# FPC-isoJTAG.net
KiCad netlist of a schematic drawn in Altium Designer
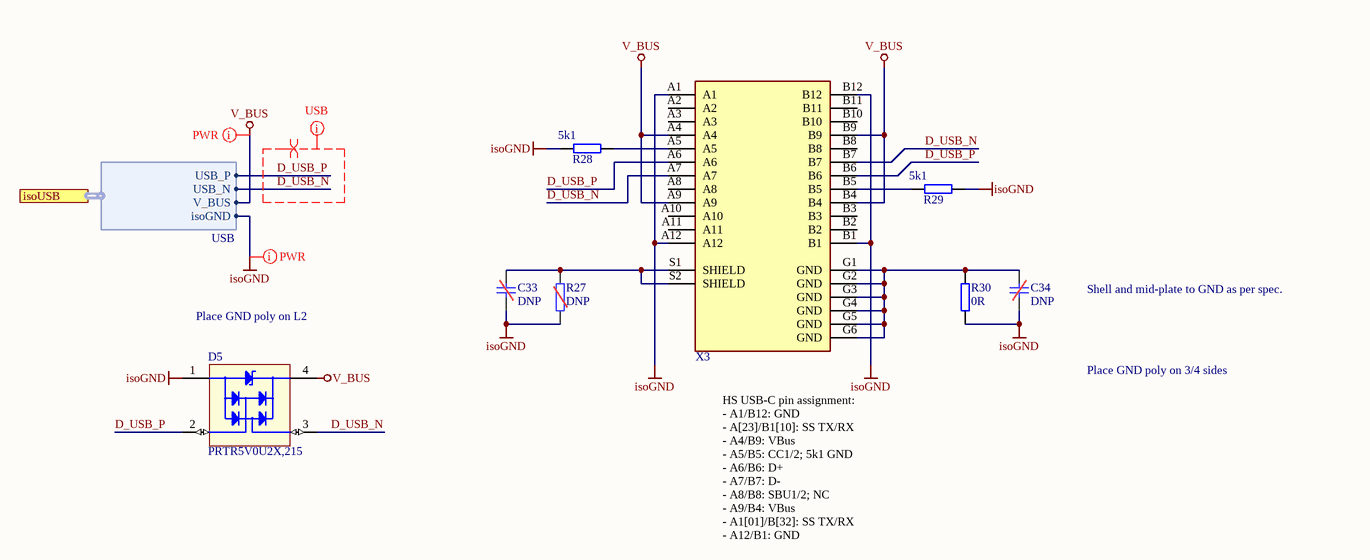
[diagram p0: FPC-isoJTAG.SchDoc]

(export (version "E")
  (design (tool "Eeschema 10.0.6"))
  (components
    (comp (ref "C33")
      (value "DNP")
      (footprint "C_1206_TE-DNP")
      (description "Generic capacitor (DNP)")
      (fields
        (field (name "MANUFACTURER PART NUMBER") "UZgen_C_1206_DNP")
        (field (name "MANUFACTURER") "UZgen")
        (field (name "CREATED FROM") "UZgenTool")
      )
      (libsource (lib "user") (part "CAP-NP-DNP"))
    )
    (comp (ref "C34")
      (value "DNP")
      (footprint "C_1206_TE-DNP")
      (description "Generic capacitor (DNP)")
      (fields
        (field (name "MANUFACTURER PART NUMBER") "UZgen_C_1206_DNP")
        (field (name "MANUFACTURER") "UZgen")
        (field (name "CREATED FROM") "UZgenTool")
      )
      (libsource (lib "user") (part "CAP-NP-DNP"))
    )
    (comp (ref "D5")
      (value "PRTR5V0U2X,215")
      (footprint "SOT-143B-4")
      (description "ESD Suppressors / TVS Diodes PRTR5V0U2X/SOT143/SOT4")
      (fields
        (field (name "MANUFACTURER") "Nexperia")
        (field (name "LCSC PART NUMBER") "C12333")
        (field (name "CREATED FROM") "AGeiger")
      )
      (libsource (lib "user") (part "CD143A-SRxx"))
    )
    (comp (ref "R27")
      (value "DNP")
      (footprint "R_1206_TE-DNP")
      (description "Generic resistor (DNP)")
      (fields
        (field (name "MANUFACTURER PART NUMBER") "UZgen_R_1206_DNP")
        (field (name "MANUFACTURER") "UZgen")
        (field (name "CREATED FROM") "UZgenTool")
      )
      (libsource (lib "user") (part "RES-DNP"))
    )
    (comp (ref "R28")
      (value "5k1")
      (footprint "R_0603_TE")
      (description "Generic resistor")
      (fields
        (field (name "MANUFACTURER PART NUMBER") "UZgen_R_0603_5k1")
        (field (name "MANUFACTURER") "UZgen")
        (field (name "CREATED FROM") "UZgenTool")
      )
      (libsource (lib "user") (part "RES"))
    )
    (comp (ref "R29")
      (value "5k1")
      (footprint "R_0603_TE")
      (description "Generic resistor")
      (fields
        (field (name "MANUFACTURER PART NUMBER") "UZgen_R_0603_5k1")
        (field (name "MANUFACTURER") "UZgen")
        (field (name "CREATED FROM") "UZgenTool")
      )
      (libsource (lib "user") (part "RES"))
    )
    (comp (ref "R30")
      (value "0R")
      (footprint "R_1206_TE")
      (description "Generic resistor")
      (fields
        (field (name "MANUFACTURER PART NUMBER") "UZgen_R_1206_0R")
        (field (name "MANUFACTURER") "UZgen")
        (field (name "CREATED FROM") "UZgenTool")
      )
      (libsource (lib "user") (part "RES"))
    )
    (comp (ref "X3")
      (value "~")
      (footprint "AMPHENOL_MUSBRM1C130_CUSTOMPADLEN3.05mm")
      (description "USB Connectors RUGGED TYPE C RIGHT ANGLE")
      (fields
        (field (name "MANUFACTURER PART NUMBER") "MUSBRM1C1M0")
        (field (name "MANUFACTURER") "Amphenol")
        (field (name "CREATED FROM") "FRosner")
      )
      (libsource (lib "user") (part "MUSBRM1C130"))
    )
  )
  (nets
    (net (code "2") (name "/D_USB_N") (class "Default")
      (node (ref "D5") (pin "3") (pinfunction "I/O_3") (pintype "bidirectional"))
      (node (ref "X3") (pin "A7") (pinfunction "A7_A7") (pintype "passive"))
      (node (ref "X3") (pin "B7") (pinfunction "B7_B7") (pintype "passive"))
    )
    (net (code "3") (name "/D_USB_P") (class "Default")
      (node (ref "D5") (pin "2") (pinfunction "I/O_2") (pintype "bidirectional"))
      (node (ref "X3") (pin "A6") (pinfunction "A6_A6") (pintype "passive"))
      (node (ref "X3") (pin "B6") (pinfunction "B6_B6") (pintype "passive"))
    )
    (net (code "5") (name "Net-(C33-Pad2)") (class "Default")
      (node (ref "C33") (pin "2") (pinfunction "2_2") (pintype "passive"))
      (node (ref "R27") (pin "2") (pinfunction "2_2") (pintype "passive"))
      (node (ref "X3") (pin "S1") (pinfunction "SHIELD_S1") (pintype "passive"))
      (node (ref "X3") (pin "S2") (pinfunction "SHIELD_S2") (pintype "passive"))
    )
    (net (code "6") (name "Net-(C34-Pad2)") (class "Default")
      (node (ref "C34") (pin "2") (pinfunction "2_2") (pintype "passive"))
      (node (ref "R30") (pin "2") (pinfunction "2_2") (pintype "passive"))
      (node (ref "X3") (pin "G1") (pinfunction "GND_G1") (pintype "power_in"))
      (node (ref "X3") (pin "G2") (pinfunction "GND_G2") (pintype "power_in"))
      (node (ref "X3") (pin "G3") (pinfunction "GND_G3") (pintype "power_in"))
      (node (ref "X3") (pin "G4") (pinfunction "GND_G4") (pintype "power_in"))
      (node (ref "X3") (pin "G5") (pinfunction "GND_G5") (pintype "power_in"))
      (node (ref "X3") (pin "G6") (pinfunction "GND_G6") (pintype "power_in"))
    )
    (net (code "7") (name "Net-(R28-Pad2)") (class "Default")
      (node (ref "R28") (pin "2") (pinfunction "2_2") (pintype "passive"))
      (node (ref "X3") (pin "A5") (pinfunction "A5_A5") (pintype "passive"))
    )
    (net (code "8") (name "Net-(R29-Pad1)") (class "Default")
      (node (ref "R29") (pin "1") (pinfunction "1_1") (pintype "passive"))
      (node (ref "X3") (pin "B5") (pinfunction "B5_B5") (pintype "passive"))
    )
    (net (code "9") (name "V_BUS") (class "Default")
      (node (ref "D5") (pin "4") (pinfunction "REF_4") (pintype "passive"))
      (node (ref "X3") (pin "A4") (pinfunction "A4_A4") (pintype "passive"))
      (node (ref "X3") (pin "A9") (pinfunction "A9_A9") (pintype "passive"))
      (node (ref "X3") (pin "B4") (pinfunction "B4_B4") (pintype "passive"))
      (node (ref "X3") (pin "B9") (pinfunction "B9_B9") (pintype "passive"))
    )
    (net (code "10") (name "isoGND") (class "Default")
      (node (ref "C33") (pin "1") (pinfunction "1_1") (pintype "passive"))
      (node (ref "C34") (pin "1") (pinfunction "1_1") (pintype "passive"))
      (node (ref "D5") (pin "1") (pinfunction "GND_1") (pintype "passive"))
      (node (ref "R27") (pin "1") (pinfunction "1_1") (pintype "passive"))
      (node (ref "R28") (pin "1") (pinfunction "1_1") (pintype "passive"))
      (node (ref "R29") (pin "2") (pinfunction "2_2") (pintype "passive"))
      (node (ref "R30") (pin "1") (pinfunction "1_1") (pintype "passive"))
      (node (ref "X3") (pin "A1") (pinfunction "A1_A1") (pintype "passive"))
      (node (ref "X3") (pin "A12") (pinfunction "A12_A12") (pintype "passive"))
      (node (ref "X3") (pin "B1") (pinfunction "B1_B1") (pintype "passive"))
      (node (ref "X3") (pin "B12") (pinfunction "B12_B12") (pintype "passive"))
    )
    (net (code "11") (name "unconnected-(X3-PadA2)") (class "Default")
      (node (ref "X3") (pin "A2") (pinfunction "A2_A2") (pintype "passive"))
    )
    (net (code "12") (name "unconnected-(X3-PadA3)") (class "Default")
      (node (ref "X3") (pin "A3") (pinfunction "A3_A3") (pintype "passive"))
    )
    (net (code "13") (name "unconnected-(X3-PadA8)") (class "Default")
      (node (ref "X3") (pin "A8") (pinfunction "A8_A8") (pintype "passive"))
    )
    (net (code "14") (name "unconnected-(X3-PadA10)") (class "Default")
      (node (ref "X3") (pin "A10") (pinfunction "A10_A10") (pintype "passive"))
    )
    (net (code "15") (name "unconnected-(X3-PadA11)") (class "Default")
      (node (ref "X3") (pin "A11") (pinfunction "A11_A11") (pintype "passive"))
    )
    (net (code "16") (name "unconnected-(X3-PadB2)") (class "Default")
      (node (ref "X3") (pin "B2") (pinfunction "B2_B2") (pintype "passive"))
    )
    (net (code "17") (name "unconnected-(X3-PadB3)") (class "Default")
      (node (ref "X3") (pin "B3") (pinfunction "B3_B3") (pintype "passive"))
    )
    (net (code "18") (name "unconnected-(X3-PadB8)") (class "Default")
      (node (ref "X3") (pin "B8") (pinfunction "B8_B8") (pintype "passive"))
    )
    (net (code "19") (name "unconnected-(X3-PadB10)") (class "Default")
      (node (ref "X3") (pin "B10") (pinfunction "B10_B10") (pintype "passive"))
    )
    (net (code "20") (name "unconnected-(X3-PadB11)") (class "Default")
      (node (ref "X3") (pin "B11") (pinfunction "B11_B11") (pintype "passive"))
    )
  )
)
